# Duinopeak_Shield_Bot_v0_9.net
KiCad netlist of a schematic drawn in EAGLE
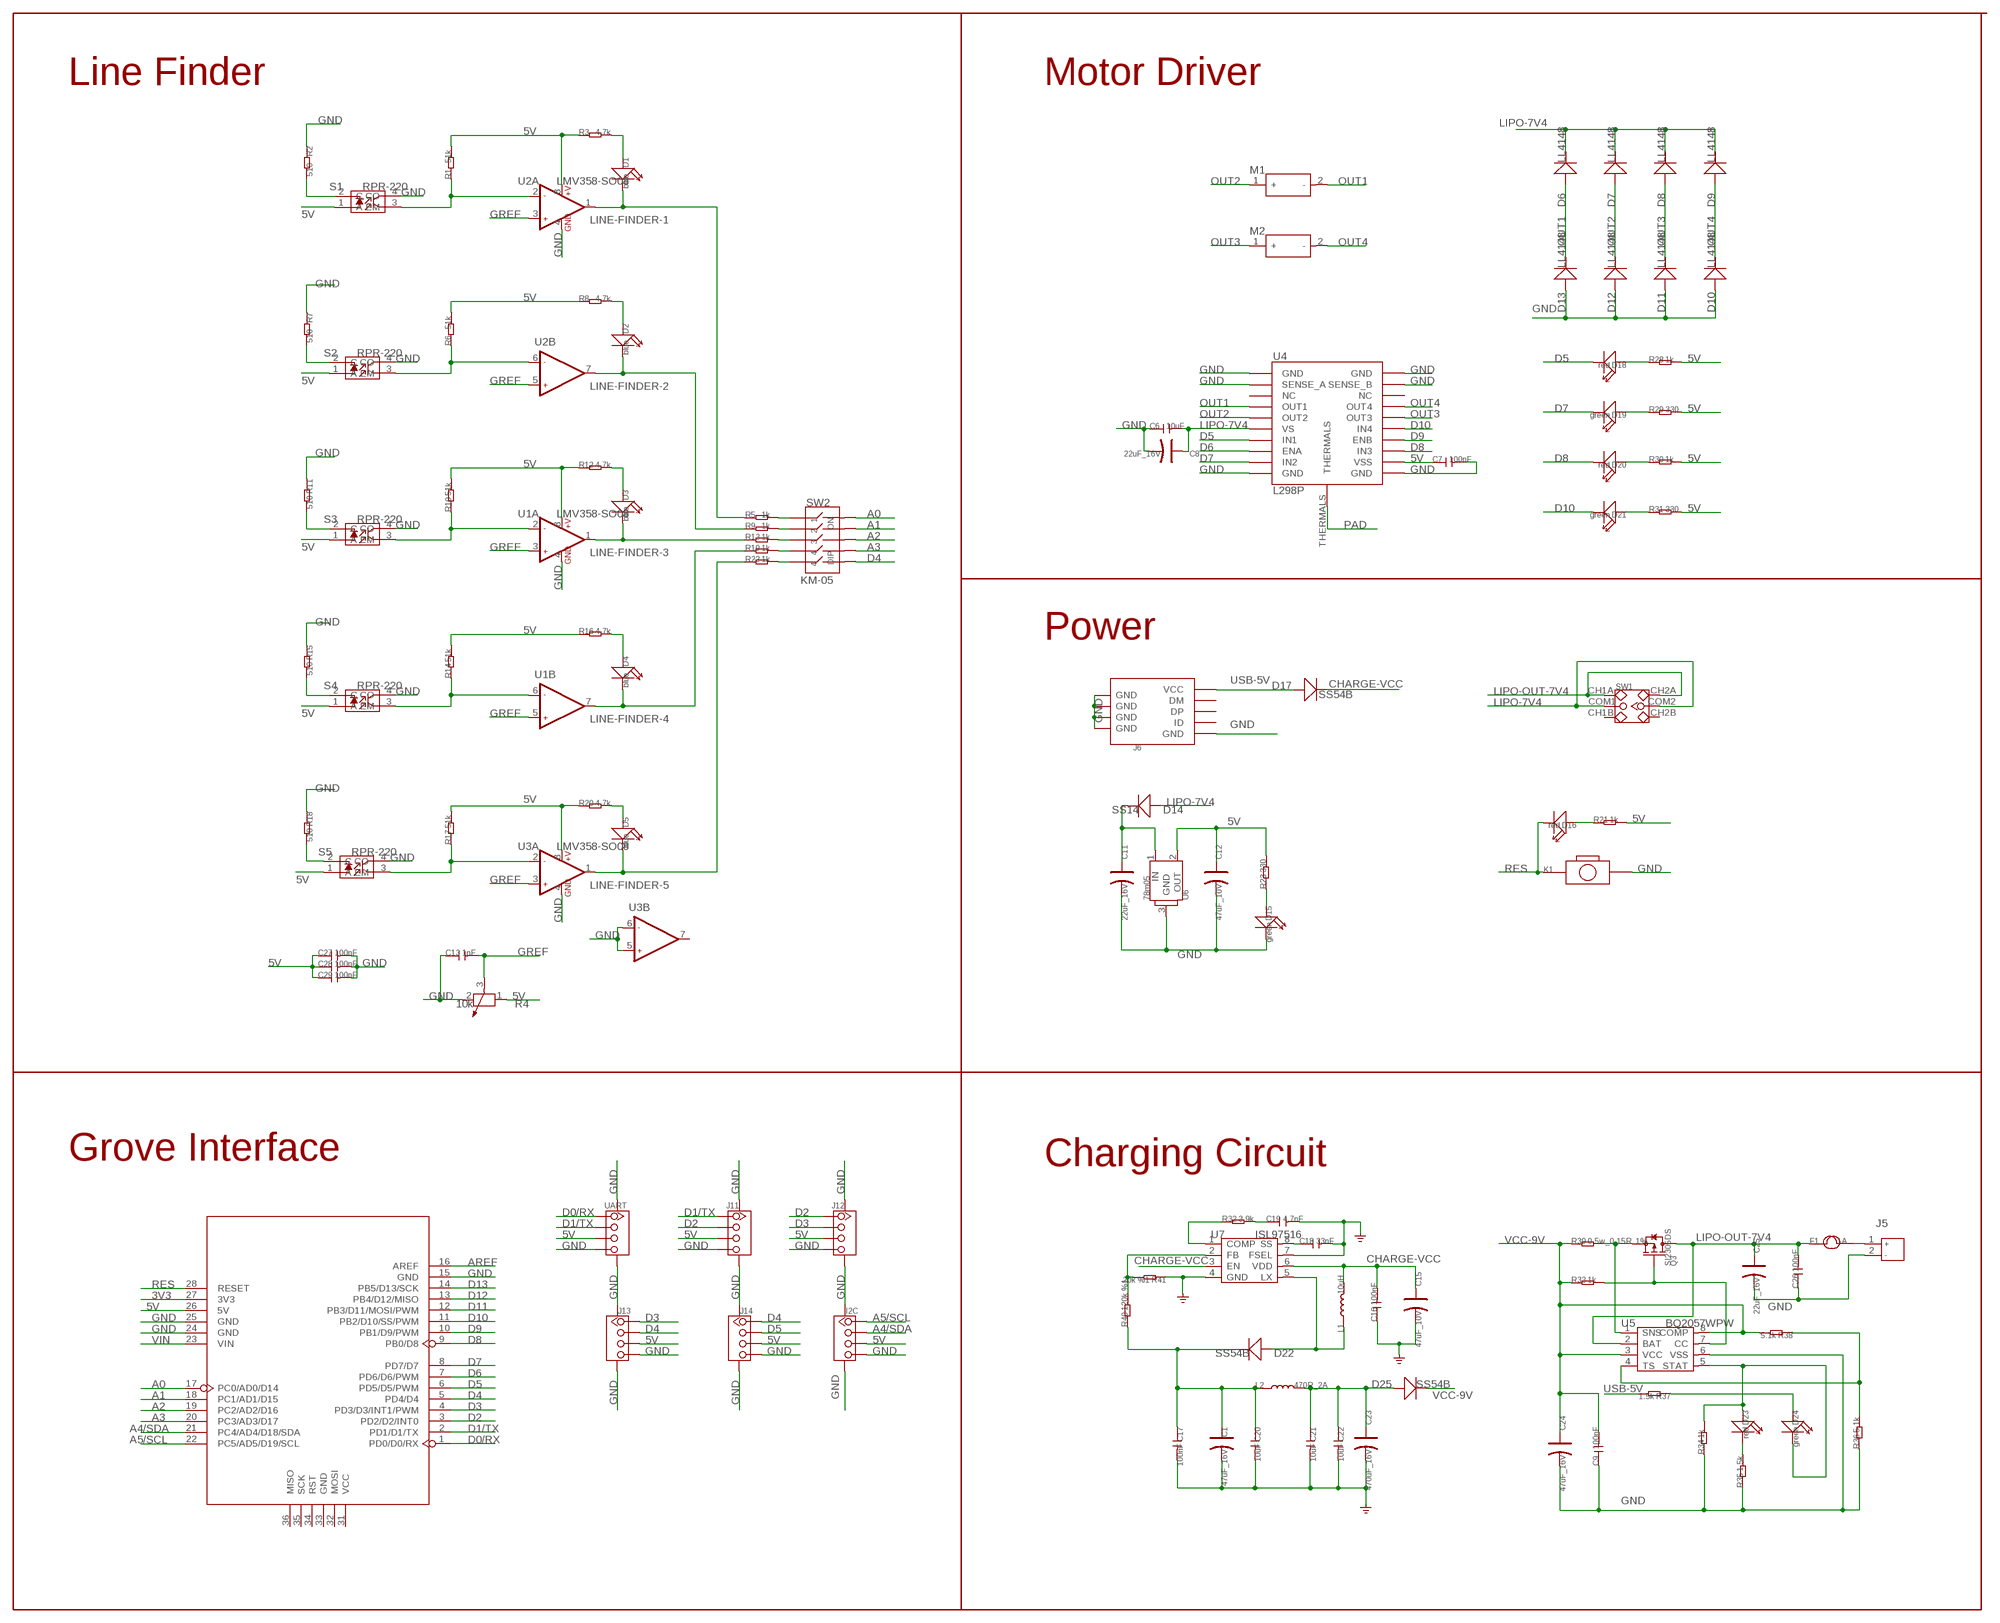
[diagram p0: schematic, sheet 1]

(export (version "E")
  (design (tool "Eeschema 10.0.6"))
  (components
    (comp (ref "C1")
      (value "47uF_16V")
      (footprint "eagle-import:AVX-C")
      (libsource (lib "eagle-import") (part "CAP-AVX-C"))
    )
    (comp (ref "C6")
      (value "10uF")
      (footprint "eagle-import:C0603")
      (libsource (lib "eagle-import") (part "C-0603"))
    )
    (comp (ref "C7")
      (value "100nF")
      (footprint "eagle-import:C0603")
      (libsource (lib "eagle-import") (part "C-0603"))
    )
    (comp (ref "C8")
      (value "22uF_16V")
      (footprint "eagle-import:AVX-B")
      (libsource (lib "eagle-import") (part "CAP-AVX-B"))
    )
    (comp (ref "C9")
      (value "100nF")
      (footprint "eagle-import:C0603")
      (libsource (lib "eagle-import") (part "C-0603"))
    )
    (comp (ref "C11")
      (value "22uF_16V")
      (footprint "eagle-import:AVX-B")
      (libsource (lib "eagle-import") (part "CAP-AVX-B"))
    )
    (comp (ref "C12")
      (value "47uF_10V")
      (footprint "eagle-import:AVX-B")
      (libsource (lib "eagle-import") (part "CAP-AVX-B"))
    )
    (comp (ref "C13")
      (value "1nF")
      (footprint "eagle-import:C0603")
      (libsource (lib "eagle-import") (part "C-0603"))
    )
    (comp (ref "C15")
      (value "47uF_10V")
      (footprint "eagle-import:AVX-B")
      (libsource (lib "eagle-import") (part "CAP-AVX-B"))
    )
    (comp (ref "C16")
      (value "100nF")
      (footprint "eagle-import:C0603")
      (libsource (lib "eagle-import") (part "C-0603"))
    )
    (comp (ref "C17")
      (value "100nF")
      (footprint "eagle-import:C0603")
      (libsource (lib "eagle-import") (part "C-0603"))
    )
    (comp (ref "C18")
      (value "33nF")
      (footprint "eagle-import:C0603")
      (libsource (lib "eagle-import") (part "C-0603"))
    )
    (comp (ref "C19")
      (value "4.7nF")
      (footprint "eagle-import:C0603")
      (libsource (lib "eagle-import") (part "C-0603"))
    )
    (comp (ref "C20")
      (value "10uF")
      (footprint "eagle-import:C0603")
      (libsource (lib "eagle-import") (part "C-0603"))
    )
    (comp (ref "C21")
      (value "10uF")
      (footprint "eagle-import:C0603")
      (libsource (lib "eagle-import") (part "C-0603"))
    )
    (comp (ref "C22")
      (value "10uF")
      (footprint "eagle-import:C0603")
      (libsource (lib "eagle-import") (part "C-0603"))
    )
    (comp (ref "C23")
      (value "470uF_16V")
      (footprint "eagle-import:AVX-E")
      (libsource (lib "eagle-import") (part "CAP-AVX-E"))
    )
    (comp (ref "C24")
      (value "47uF_16V")
      (footprint "eagle-import:AVX-C")
      (libsource (lib "eagle-import") (part "CAP-AVX-C"))
    )
    (comp (ref "C25")
      (value "22uF_16V")
      (footprint "eagle-import:AVX-B")
      (libsource (lib "eagle-import") (part "CAP-AVX-B"))
    )
    (comp (ref "C26")
      (value "100nF")
      (footprint "eagle-import:C0603")
      (libsource (lib "eagle-import") (part "C-0603"))
    )
    (comp (ref "C27")
      (value "100nF")
      (footprint "eagle-import:C0603")
      (libsource (lib "eagle-import") (part "C-0603"))
    )
    (comp (ref "C28")
      (value "100nF")
      (footprint "eagle-import:C0603")
      (libsource (lib "eagle-import") (part "C-0603"))
    )
    (comp (ref "C29")
      (value "100nF")
      (footprint "eagle-import:C0603")
      (libsource (lib "eagle-import") (part "C-0603"))
    )
    (comp (ref "D1")
      (value "blue")
      (footprint "eagle-import:LED-0603")
      (libsource (lib "eagle-import") (part "LED'0603'"))
    )
    (comp (ref "D2")
      (value "blue")
      (footprint "eagle-import:LED-0603")
      (libsource (lib "eagle-import") (part "LED'0603'"))
    )
    (comp (ref "D3")
      (value "blue")
      (footprint "eagle-import:LED-0603")
      (libsource (lib "eagle-import") (part "LED'0603'"))
    )
    (comp (ref "D4")
      (value "blue")
      (footprint "eagle-import:LED-0603")
      (libsource (lib "eagle-import") (part "LED'0603'"))
    )
    (comp (ref "D5")
      (value "blue")
      (footprint "eagle-import:LED-0603")
      (libsource (lib "eagle-import") (part "LED'0603'"))
    )
    (comp (ref "D6")
      (value "LL4148")
      (footprint "eagle-import:SOD123")
      (libsource (lib "eagle-import") (part "D'1206'"))
    )
    (comp (ref "D7")
      (value "LL4148")
      (footprint "eagle-import:SOD123")
      (libsource (lib "eagle-import") (part "D'1206'"))
    )
    (comp (ref "D8")
      (value "LL4148")
      (footprint "eagle-import:SOD123")
      (libsource (lib "eagle-import") (part "D'1206'"))
    )
    (comp (ref "D9")
      (value "LL4148")
      (footprint "eagle-import:SOD123")
      (libsource (lib "eagle-import") (part "D'1206'"))
    )
    (comp (ref "D10")
      (value "LL4148")
      (footprint "eagle-import:SOD123")
      (libsource (lib "eagle-import") (part "D'1206'"))
    )
    (comp (ref "D11")
      (value "LL4148")
      (footprint "eagle-import:SOD123")
      (libsource (lib "eagle-import") (part "D'1206'"))
    )
    (comp (ref "D12")
      (value "LL4148")
      (footprint "eagle-import:SOD123")
      (libsource (lib "eagle-import") (part "D'1206'"))
    )
    (comp (ref "D13")
      (value "LL4148")
      (footprint "eagle-import:SOD123")
      (libsource (lib "eagle-import") (part "D'1206'"))
    )
    (comp (ref "D14")
      (value "SS14")
      (footprint "eagle-import:D2010")
      (libsource (lib "eagle-import") (part "D'SMA'"))
    )
    (comp (ref "D15")
      (value "green")
      (footprint "eagle-import:LED-0603")
      (libsource (lib "eagle-import") (part "LED'0603'"))
    )
    (comp (ref "D16")
      (value "red")
      (footprint "eagle-import:LED-0603")
      (libsource (lib "eagle-import") (part "LED'0603'"))
    )
    (comp (ref "D17")
      (value "SS54B")
      (footprint "eagle-import:SMB")
      (libsource (lib "eagle-import") (part "D'MBRS240LT3'"))
    )
    (comp (ref "D18")
      (value "red")
      (footprint "eagle-import:LED-0603")
      (libsource (lib "eagle-import") (part "LED'0603'"))
    )
    (comp (ref "D19")
      (value "green")
      (footprint "eagle-import:LED-0603")
      (libsource (lib "eagle-import") (part "LED'0603'"))
    )
    (comp (ref "D20")
      (value "red")
      (footprint "eagle-import:LED-0603")
      (libsource (lib "eagle-import") (part "LED'0603'"))
    )
    (comp (ref "D21")
      (value "green")
      (footprint "eagle-import:LED-0603")
      (libsource (lib "eagle-import") (part "LED'0603'"))
    )
    (comp (ref "D22")
      (value "SS54B")
      (footprint "eagle-import:SMB")
      (libsource (lib "eagle-import") (part "D'MBRS240LT3'"))
    )
    (comp (ref "D23")
      (value "red")
      (footprint "eagle-import:LED-0603")
      (libsource (lib "eagle-import") (part "LED'0603'"))
    )
    (comp (ref "D24")
      (value "green")
      (footprint "eagle-import:LED-0603")
      (libsource (lib "eagle-import") (part "LED'0603'"))
    )
    (comp (ref "D25")
      (value "SS54B")
      (footprint "eagle-import:SMB")
      (libsource (lib "eagle-import") (part "D'MBRS240LT3'"))
    )
    (comp (ref "F1")
      (value "1A")
      (footprint "eagle-import:1812")
      (libsource (lib "eagle-import") (part "FUSE"))
    )
    (comp (ref "I2C")
      (value "TWIG-4P-2.0-SMD-FEMALE-REINFORCE'90D'")
      (footprint "eagle-import:4P-SMD-2.0-90D")
      (libsource (lib "eagle-import") (part "TWIG-4P-2.0-SMD-FEMALE-REINFORCE'90D'"))
    )
    (comp (ref "J5")
      (value "JACK-JST-2P-PW'2.0'")
      (footprint "eagle-import:JST-2.0")
      (libsource (lib "eagle-import") (part "JACK-JST-2P-PW'2.0'"))
    )
    (comp (ref "J6")
      (value "USB-MINIUSB-5P-STRONG")
      (footprint "eagle-import:MINI-SMD-5P")
      (libsource (lib "eagle-import") (part "USB-MINIUSB-5P-STRONG"))
    )
    (comp (ref "J11")
      (value "TWIG-4P-2.0-SMD-FEMALE-REINFORCE'90D'")
      (footprint "eagle-import:4P-SMD-2.0-90D")
      (libsource (lib "eagle-import") (part "TWIG-4P-2.0-SMD-FEMALE-REINFORCE'90D'"))
    )
    (comp (ref "J12")
      (value "TWIG-4P-2.0-SMD-FEMALE-REINFORCE'90D'")
      (footprint "eagle-import:4P-SMD-2.0-90D")
      (libsource (lib "eagle-import") (part "TWIG-4P-2.0-SMD-FEMALE-REINFORCE'90D'"))
    )
    (comp (ref "J13")
      (value "TWIG-4P-2.0-SMD-FEMALE-REINFORCE'90D'")
      (footprint "eagle-import:4P-SMD-2.0-90D")
      (libsource (lib "eagle-import") (part "TWIG-4P-2.0-SMD-FEMALE-REINFORCE'90D'"))
    )
    (comp (ref "J14")
      (value "TWIG-4P-2.0-SMD-FEMALE-REINFORCE'90D'")
      (footprint "eagle-import:4P-SMD-2.0-90D")
      (libsource (lib "eagle-import") (part "TWIG-4P-2.0-SMD-FEMALE-REINFORCE'90D'"))
    )
    (comp (ref "K1")
      (value "BOTTON-2P-90D")
      (footprint "eagle-import:2P-7.62X3.56-90D")
      (libsource (lib "eagle-import") (part "BOTTON-2P-90D"))
    )
    (comp (ref "L1")
      (value "10uH")
      (footprint "eagle-import:2626")
      (libsource (lib "eagle-import") (part "L'IHLP-2525BD-01'"))
    )
    (comp (ref "L2")
      (value "470R_2A")
      (footprint "eagle-import:L0805")
      (libsource (lib "eagle-import") (part "L'0805'"))
    )
    (comp (ref "M1")
      (value "MOTOR-2P-PAD")
      (footprint "eagle-import:2P-SMD-27X26")
      (libsource (lib "eagle-import") (part "MOTOR-2P-PAD"))
    )
    (comp (ref "M2")
      (value "MOTOR-2P-PAD")
      (footprint "eagle-import:2P-SMD-27X26")
      (libsource (lib "eagle-import") (part "MOTOR-2P-PAD"))
    )
    (comp (ref "Q3")
      (value "SI2305DS")
      (footprint "eagle-import:SOT23")
      (libsource (lib "eagle-import") (part "MOSFET-P'SI2323CDS/SI2305DS{lt}BR{gt}'"))
    )
    (comp (ref "R1")
      (value "51k")
      (footprint "eagle-import:R0603")
      (libsource (lib "eagle-import") (part "R-0603"))
    )
    (comp (ref "R2")
      (value "510")
      (footprint "eagle-import:R0603")
      (libsource (lib "eagle-import") (part "R-0603"))
    )
    (comp (ref "R3")
      (value "4.7k")
      (footprint "eagle-import:R0603")
      (libsource (lib "eagle-import") (part "R-0603"))
    )
    (comp (ref "R4")
      (value "10k")
      (footprint "eagle-import:3P-SQUA-7X6.8")
      (libsource (lib "eagle-import") (part "R-POTENTIOMETER'3362'"))
    )
    (comp (ref "R5")
      (value "1k")
      (footprint "eagle-import:R0603")
      (libsource (lib "eagle-import") (part "R-0603"))
    )
    (comp (ref "R6")
      (value "51k")
      (footprint "eagle-import:R0603")
      (libsource (lib "eagle-import") (part "R-0603"))
    )
    (comp (ref "R7")
      (value "510")
      (footprint "eagle-import:R0603")
      (libsource (lib "eagle-import") (part "R-0603"))
    )
    (comp (ref "R8")
      (value "4.7k")
      (footprint "eagle-import:R0603")
      (libsource (lib "eagle-import") (part "R-0603"))
    )
    (comp (ref "R9")
      (value "1k")
      (footprint "eagle-import:R0603")
      (libsource (lib "eagle-import") (part "R-0603"))
    )
    (comp (ref "R10")
      (value "51k")
      (footprint "eagle-import:R0603")
      (libsource (lib "eagle-import") (part "R-0603"))
    )
    (comp (ref "R11")
      (value "510")
      (footprint "eagle-import:R0603")
      (libsource (lib "eagle-import") (part "R-0603"))
    )
    (comp (ref "R12")
      (value "4.7k")
      (footprint "eagle-import:R0603")
      (libsource (lib "eagle-import") (part "R-0603"))
    )
    (comp (ref "R13")
      (value "1k")
      (footprint "eagle-import:R0603")
      (libsource (lib "eagle-import") (part "R-0603"))
    )
    (comp (ref "R14")
      (value "51k")
      (footprint "eagle-import:R0603")
      (libsource (lib "eagle-import") (part "R-0603"))
    )
    (comp (ref "R15")
      (value "510")
      (footprint "eagle-import:R0603")
      (libsource (lib "eagle-import") (part "R-0603"))
    )
    (comp (ref "R16")
      (value "4.7k")
      (footprint "eagle-import:R0603")
      (libsource (lib "eagle-import") (part "R-0603"))
    )
    (comp (ref "R17")
      (value "51k")
      (footprint "eagle-import:R0603")
      (libsource (lib "eagle-import") (part "R-0603"))
    )
    (comp (ref "R18")
      (value "510")
      (footprint "eagle-import:R0603")
      (libsource (lib "eagle-import") (part "R-0603"))
    )
    (comp (ref "R19")
      (value "1k")
      (footprint "eagle-import:R0603")
      (libsource (lib "eagle-import") (part "R-0603"))
    )
    (comp (ref "R20")
      (value "4.7k")
      (footprint "eagle-import:R0603")
      (libsource (lib "eagle-import") (part "R-0603"))
    )
    (comp (ref "R21")
      (value "1k")
      (footprint "eagle-import:R0603")
      (libsource (lib "eagle-import") (part "R-0603"))
    )
    (comp (ref "R22")
      (value "1k")
      (footprint "eagle-import:R0603")
      (libsource (lib "eagle-import") (part "R-0603"))
    )
    (comp (ref "R23")
      (value "330")
      (footprint "eagle-import:R0603")
      (libsource (lib "eagle-import") (part "R-0603"))
    )
    (comp (ref "R28")
      (value "1k")
      (footprint "eagle-import:R0603")
      (libsource (lib "eagle-import") (part "R-0603"))
    )
    (comp (ref "R29")
      (value "330")
      (footprint "eagle-import:R0603")
      (libsource (lib "eagle-import") (part "R-0603"))
    )
    (comp (ref "R30")
      (value "1k")
      (footprint "eagle-import:R0603")
      (libsource (lib "eagle-import") (part "R-0603"))
    )
    (comp (ref "R31")
      (value "330")
      (footprint "eagle-import:R0603")
      (libsource (lib "eagle-import") (part "R-0603"))
    )
    (comp (ref "R32")
      (value "3.9k")
      (footprint "eagle-import:R0603")
      (libsource (lib "eagle-import") (part "R-0603"))
    )
    (comp (ref "R33")
      (value "1k")
      (footprint "eagle-import:R0603")
      (libsource (lib "eagle-import") (part "R-0603"))
    )
    (comp (ref "R34")
      (value "1k")
      (footprint "eagle-import:R0603")
      (libsource (lib "eagle-import") (part "R-0603"))
    )
    (comp (ref "R35")
      (value "1.5k")
      (footprint "eagle-import:R0603")
      (libsource (lib "eagle-import") (part "R-0603"))
    )
    (comp (ref "R36")
      (value "5.1k")
      (footprint "eagle-import:R0603")
      (libsource (lib "eagle-import") (part "R-0603"))
    )
    (comp (ref "R37")
      (value "1.5k")
      (footprint "eagle-import:R0603")
      (libsource (lib "eagle-import") (part "R-0603"))
    )
    (comp (ref "R38")
      (value "5.1k")
      (footprint "eagle-import:R0603")
      (libsource (lib "eagle-import") (part "R-0603"))
    )
    (comp (ref "R39")
      (value "0.5w_0.15R 1%")
      (footprint "eagle-import:R2512")
      (libsource (lib "eagle-import") (part "R-2512"))
    )
    (comp (ref "R40")
      (value "120k %1")
      (footprint "eagle-import:R0603")
      (libsource (lib "eagle-import") (part "R-0603"))
    )
    (comp (ref "R41")
      (value "20k %1")
      (footprint "eagle-import:R0603")
      (libsource (lib "eagle-import") (part "R-0603"))
    )
    (comp (ref "S1")
      (value "RPR-220")
      (footprint "eagle-import:4P-6.4X4.9X6.5H")
      (libsource (lib "eagle-import") (part "REFLECTIVE-PHOTOSENSOR-RPR-220"))
    )
    (comp (ref "S2")
      (value "RPR-220")
      (footprint "eagle-import:4P-6.4X4.9X6.5H")
      (libsource (lib "eagle-import") (part "REFLECTIVE-PHOTOSENSOR-RPR-220"))
    )
    (comp (ref "S3")
      (value "RPR-220")
      (footprint "eagle-import:4P-6.4X4.9X6.5H")
      (libsource (lib "eagle-import") (part "REFLECTIVE-PHOTOSENSOR-RPR-220"))
    )
    (comp (ref "S4")
      (value "RPR-220")
      (footprint "eagle-import:4P-6.4X4.9X6.5H")
      (libsource (lib "eagle-import") (part "REFLECTIVE-PHOTOSENSOR-RPR-220"))
    )
    (comp (ref "S5")
      (value "RPR-220")
      (footprint "eagle-import:4P-6.4X4.9X6.5H")
      (libsource (lib "eagle-import") (part "REFLECTIVE-PHOTOSENSOR-RPR-220"))
    )
    (comp (ref "SW1")
      (value "SWITCH-2CH-6P'90D'")
      (footprint "eagle-import:6P-2CH-2.54-9.0X3.6-90D")
      (libsource (lib "eagle-import") (part "SWITCH-2CH-6P'90D'"))
    )
    (comp (ref "SW2")
      (value "KM-05")
      (footprint "eagle-import:10P-SMD-14.2X6.8")
      (libsource (lib "eagle-import") (part "SWITCH-KM-05-10P"))
    )
    (comp (ref "U1")
      (value "LMV358-SO08")
      (footprint "eagle-import:SO08")
      (libsource (lib "eagle-import") (part "LMV358-SO08"))
    )
    (comp (ref "U2")
      (value "LMV358-SO08")
      (footprint "eagle-import:SO08")
      (libsource (lib "eagle-import") (part "LMV358-SO08"))
    )
    (comp (ref "U3")
      (value "LMV358-SO08")
      (footprint "eagle-import:SO08")
      (libsource (lib "eagle-import") (part "LMV358-SO08"))
    )
    (comp (ref "U4")
      (value "L298P")
      (footprint "eagle-import:POWERSO20")
      (libsource (lib "eagle-import") (part "L298_BRIDGE_DRIVER"))
    )
    (comp (ref "U5")
      (value "BQ2057WPW")
      (footprint "eagle-import:TSSOP8")
      (libsource (lib "eagle-import") (part "BQ2057WPW"))
    )
    (comp (ref "U6")
      (value "78m05")
      (footprint "eagle-import:TO252")
      (libsource (lib "eagle-import") (part "78M05-TO252"))
    )
    (comp (ref "U7")
      (value "ISL97516")
      (footprint "eagle-import:MSOP8")
      (libsource (lib "eagle-import") (part "ISL97516"))
    )
    (comp (ref "U13")
      (value "ARDUINO")
      (footprint "eagle-import:ARDUINO")
      (libsource (lib "eagle-import") (part "ARDUINO"))
    )
    (comp (ref "UART")
      (value "TWIG-4P-2.0-SMD-FEMALE-REINFORCE'90D'")
      (footprint "eagle-import:4P-SMD-2.0-90D")
      (libsource (lib "eagle-import") (part "TWIG-4P-2.0-SMD-FEMALE-REINFORCE'90D'"))
    )
  )
  (nets
    (net (code "1") (name "/3V3") (class "Default")
      (node (ref "U13") (pin "27") (pinfunction "3V3_27") (pintype "bidirectional"))
    )
    (net (code "2") (name "/5V") (class "Default")
      (node (ref "C12") (pin "+") (pinfunction "+_+") (pintype "passive"))
      (node (ref "C27") (pin "1") (pinfunction "1_1") (pintype "passive"))
      (node (ref "C28") (pin "1") (pinfunction "1_1") (pintype "passive"))
      (node (ref "C29") (pin "1") (pinfunction "1_1") (pintype "passive"))
      (node (ref "C7") (pin "1") (pinfunction "1_1") (pintype "passive"))
      (node (ref "I2C") (pin "3") (pinfunction "3_3") (pintype "bidirectional"))
      (node (ref "J11") (pin "3") (pinfunction "3_3") (pintype "bidirectional"))
      (node (ref "J12") (pin "3") (pinfunction "3_3") (pintype "bidirectional"))
      (node (ref "J13") (pin "3") (pinfunction "3_3") (pintype "bidirectional"))
      (node (ref "J14") (pin "3") (pinfunction "3_3") (pintype "bidirectional"))
      (node (ref "R1") (pin "2") (pinfunction "2_2") (pintype "passive"))
      (node (ref "R10") (pin "2") (pinfunction "2_2") (pintype "passive"))
      (node (ref "R12") (pin "1") (pinfunction "1_1") (pintype "passive"))
      (node (ref "R14") (pin "2") (pinfunction "2_2") (pintype "passive"))
      (node (ref "R16") (pin "1") (pinfunction "1_1") (pintype "passive"))
      (node (ref "R17") (pin "2") (pinfunction "2_2") (pintype "passive"))
      (node (ref "R20") (pin "1") (pinfunction "1_1") (pintype "passive"))
      (node (ref "R21") (pin "2") (pinfunction "2_2") (pintype "passive"))
      (node (ref "R23") (pin "2") (pinfunction "2_2") (pintype "passive"))
      (node (ref "R28") (pin "2") (pinfunction "2_2") (pintype "passive"))
      (node (ref "R29") (pin "2") (pinfunction "2_2") (pintype "passive"))
      (node (ref "R3") (pin "1") (pinfunction "1_1") (pintype "passive"))
      (node (ref "R30") (pin "2") (pinfunction "2_2") (pintype "passive"))
      (node (ref "R31") (pin "2") (pinfunction "2_2") (pintype "passive"))
      (node (ref "R4") (pin "1") (pinfunction "1_1") (pintype "passive"))
      (node (ref "R6") (pin "2") (pinfunction "2_2") (pintype "passive"))
      (node (ref "R8") (pin "1") (pinfunction "1_1") (pintype "passive"))
      (node (ref "S1") (pin "1") (pinfunction "A_1") (pintype "bidirectional"))
      (node (ref "S2") (pin "1") (pinfunction "A_1") (pintype "bidirectional"))
      (node (ref "S3") (pin "1") (pinfunction "A_1") (pintype "bidirectional"))
      (node (ref "S4") (pin "1") (pinfunction "A_1") (pintype "bidirectional"))
      (node (ref "S5") (pin "1") (pinfunction "A_1") (pintype "bidirectional"))
      (node (ref "U1") (pin "8") (pinfunction "+V_8") (pintype "power_in"))
      (node (ref "U13") (pin "26") (pinfunction "5V_26") (pintype "bidirectional"))
      (node (ref "U2") (pin "8") (pinfunction "+V_8") (pintype "power_in"))
      (node (ref "U3") (pin "8") (pinfunction "+V_8") (pintype "power_in"))
      (node (ref "U4") (pin "P$12") (pinfunction "VSS_P$12") (pintype "bidirectional"))
      (node (ref "U6") (pin "2") (pinfunction "OUT_2") (pintype "bidirectional"))
      (node (ref "UART") (pin "3") (pinfunction "3_3") (pintype "bidirectional"))
    )
    (net (code "3") (name "/A0") (class "Default")
      (node (ref "SW2") (pin "10") (pinfunction "10_10") (pintype "bidirectional"))
      (node (ref "U13") (pin "17") (pinfunction "PC0/AD0/D14_17") (pintype "bidirectional"))
    )
    (net (code "4") (name "/A1") (class "Default")
      (node (ref "SW2") (pin "9") (pinfunction "9_9") (pintype "bidirectional"))
      (node (ref "U13") (pin "18") (pinfunction "PC1/AD1/D15_18") (pintype "bidirectional"))
    )
    (net (code "5") (name "/A2") (class "Default")
      (node (ref "SW2") (pin "8") (pinfunction "8_8") (pintype "bidirectional"))
      (node (ref "U13") (pin "19") (pinfunction "PC2/AD2/D16_19") (pintype "bidirectional"))
    )
    (net (code "6") (name "/A3") (class "Default")
      (node (ref "SW2") (pin "7") (pinfunction "7_7") (pintype "bidirectional"))
      (node (ref "U13") (pin "20") (pinfunction "PC3/AD3/D17_20") (pintype "bidirectional"))
    )
    (net (code "7") (name "/A4{slash}SDA") (class "Default")
      (node (ref "I2C") (pin "2") (pinfunction "2_2") (pintype "bidirectional"))
      (node (ref "U13") (pin "21") (pinfunction "PC4/AD4/D18/SDA_21") (pintype "bidirectional"))
    )
    (net (code "8") (name "/A5{slash}SCL") (class "Default")
      (node (ref "I2C") (pin "1") (pinfunction "1_1") (pintype "bidirectional"))
      (node (ref "U13") (pin "22") (pinfunction "PC5/AD5/D19/SCL_22") (pintype "bidirectional"))
    )
    (net (code "9") (name "/AREF") (class "Default")
      (node (ref "U13") (pin "16") (pinfunction "AREF_16") (pintype "bidirectional"))
    )
    (net (code "10") (name "/CHARGE-VCC") (class "Default")
      (node (ref "C15") (pin "+") (pinfunction "+_+") (pintype "passive"))
      (node (ref "C16") (pin "2") (pinfunction "2_2") (pintype "passive"))
      (node (ref "D17") (pin "-") (pinfunction "-_-") (pintype "passive"))
      (node (ref "L1") (pin "2") (pinfunction "2_2") (pintype "passive"))
      (node (ref "U7") (pin "3") (pinfunction "EN_3") (pintype "input"))
      (node (ref "U7") (pin "6") (pinfunction "VDD_6") (pintype "power_in"))
    )
    (net (code "11") (name "/D0{slash}RX") (class "Default")
      (node (ref "U13") (pin "1") (pinfunction "PD0/D0/RX_1") (pintype "bidirectional"))
      (node (ref "UART") (pin "1") (pinfunction "1_1") (pintype "bidirectional"))
    )
    (net (code "12") (name "/D1{slash}TX") (class "Default")
      (node (ref "J11") (pin "1") (pinfunction "1_1") (pintype "bidirectional"))
      (node (ref "U13") (pin "2") (pinfunction "PD1/D1/TX_2") (pintype "bidirectional"))
      (node (ref "UART") (pin "2") (pinfunction "2_2") (pintype "bidirectional"))
    )
    (net (code "13") (name "/D2") (class "Default")
      (node (ref "J11") (pin "2") (pinfunction "2_2") (pintype "bidirectional"))
      (node (ref "J12") (pin "1") (pinfunction "1_1") (pintype "bidirectional"))
      (node (ref "U13") (pin "3") (pinfunction "PD2/D2/INT0_3") (pintype "bidirectional"))
    )
    (net (code "14") (name "/D3") (class "Default")
      (node (ref "J12") (pin "2") (pinfunction "2_2") (pintype "bidirectional"))
      (node (ref "J13") (pin "1") (pinfunction "1_1") (pintype "bidirectional"))
      (node (ref "U13") (pin "4") (pinfunction "PD3/D3/INT1/PWM_4") (pintype "bidirectional"))
    )
    (net (code "15") (name "/D4") (class "Default")
      (node (ref "J13") (pin "2") (pinfunction "2_2") (pintype "bidirectional"))
      (node (ref "J14") (pin "1") (pinfunction "1_1") (pintype "bidirectional"))
      (node (ref "SW2") (pin "6") (pinfunction "6_6") (pintype "bidirectional"))
      (node (ref "U13") (pin "5") (pinfunction "PD4/D4_5") (pintype "bidirectional"))
    )
    (net (code "16") (name "/D5") (class "Default")
      (node (ref "D18") (pin "-") (pinfunction "-_-") (pintype "passive"))
      (node (ref "J14") (pin "2") (pinfunction "2_2") (pintype "bidirectional"))
      (node (ref "U13") (pin "6") (pinfunction "PD5/D5/PWM_6") (pintype "bidirectional"))
      (node (ref "U4") (pin "P$7") (pinfunction "IN1_P$7") (pintype "bidirectional"))
    )
    (net (code "17") (name "/D6") (class "Default")
      (node (ref "U13") (pin "7") (pinfunction "PD6/D6/PWM_7") (pintype "bidirectional"))
      (node (ref "U4") (pin "P$8") (pinfunction "ENA_P$8") (pintype "bidirectional"))
    )
    (net (code "18") (name "/D7") (class "Default")
      (node (ref "D19") (pin "-") (pinfunction "-_-") (pintype "passive"))
      (node (ref "U13") (pin "8") (pinfunction "PD7/D7_8") (pintype "bidirectional"))
      (node (ref "U4") (pin "P$9") (pinfunction "IN2_P$9") (pintype "bidirectional"))
    )
    (net (code "19") (name "/D8") (class "Default")
      (node (ref "D20") (pin "-") (pinfunction "-_-") (pintype "passive"))
      (node (ref "U13") (pin "9") (pinfunction "PB0/D8_9") (pintype "bidirectional"))
      (node (ref "U4") (pin "P$13") (pinfunction "IN3_P$13") (pintype "bidirectional"))
    )
    (net (code "20") (name "/D9") (class "Default")
      (node (ref "U13") (pin "10") (pinfunction "PB1/D9/PWM_10") (pintype "bidirectional"))
      (node (ref "U4") (pin "P$14") (pinfunction "ENB_P$14") (pintype "bidirectional"))
    )
    (net (code "21") (name "/D10") (class "Default")
      (node (ref "D21") (pin "-") (pinfunction "-_-") (pintype "passive"))
      (node (ref "U13") (pin "11") (pinfunction "PB2/D10/SS/PWM_11") (pintype "bidirectional"))
      (node (ref "U4") (pin "P$15") (pinfunction "IN4_P$15") (pintype "bidirectional"))
    )
    (net (code "22") (name "/D11") (class "Default")
      (node (ref "U13") (pin "12") (pinfunction "PB3/D11/MOSI/PWM_12") (pintype "bidirectional"))
    )
    (net (code "23") (name "/D12") (class "Default")
      (node (ref "U13") (pin "13") (pinfunction "PB4/D12/MISO_13") (pintype "bidirectional"))
    )
    (net (code "24") (name "/D13") (class "Default")
      (node (ref "U13") (pin "14") (pinfunction "PB5/D13/SCK_14") (pintype "bidirectional"))
    )
    (net (code "25") (name "/GREF") (class "Default")
      (node (ref "C13") (pin "2") (pinfunction "2_2") (pintype "passive"))
      (node (ref "R4") (pin "3") (pinfunction "3_3") (pintype "passive"))
      (node (ref "U1") (pin "3") (pinfunction "+IN1_3") (pintype "input"))
      (node (ref "U1") (pin "5") (pinfunction "+IN2_5") (pintype "input"))
      (node (ref "U2") (pin "3") (pinfunction "+IN1_3") (pintype "input"))
      (node (ref "U2") (pin "5") (pinfunction "+IN2_5") (pintype "input"))
      (node (ref "U3") (pin "3") (pinfunction "+IN1_3") (pintype "input"))
    )
    (net (code "26") (name "/LINE-FINDER-1") (class "Default")
      (node (ref "D1") (pin "-") (pinfunction "-_-") (pintype "passive"))
      (node (ref "R5") (pin "1") (pinfunction "1_1") (pintype "passive"))
      (node (ref "U2") (pin "1") (pinfunction "OUT1_1") (pintype "output"))
    )
    (net (code "27") (name "/LINE-FINDER-2") (class "Default")
      (node (ref "D2") (pin "-") (pinfunction "-_-") (pintype "passive"))
      (node (ref "R9") (pin "1") (pinfunction "1_1") (pintype "passive"))
      (node (ref "U2") (pin "7") (pinfunction "OUT2_7") (pintype "output"))
    )
    (net (code "28") (name "/LINE-FINDER-3") (class "Default")
      (node (ref "D3") (pin "-") (pinfunction "-_-") (pintype "passive"))
      (node (ref "R13") (pin "1") (pinfunction "1_1") (pintype "passive"))
      (node (ref "U1") (pin "1") (pinfunction "OUT1_1") (pintype "output"))
    )
    (net (code "29") (name "/LINE-FINDER-4") (class "Default")
      (node (ref "D4") (pin "-") (pinfunction "-_-") (pintype "passive"))
      (node (ref "R19") (pin "1") (pinfunction "1_1") (pintype "passive"))
      (node (ref "U1") (pin "7") (pinfunction "OUT2_7") (pintype "output"))
    )
    (net (code "30") (name "/LINE-FINDER-5") (class "Default")
      (node (ref "D5") (pin "-") (pinfunction "-_-") (pintype "passive"))
      (node (ref "R22") (pin "1") (pinfunction "1_1") (pintype "passive"))
      (node (ref "U3") (pin "1") (pinfunction "OUT1_1") (pintype "output"))
    )
    (net (code "31") (name "/LIPO-7V4") (class "Default")
      (node (ref "C6") (pin "2") (pinfunction "2_2") (pintype "passive"))
      (node (ref "C8") (pin "+") (pinfunction "+_+") (pintype "passive"))
      (node (ref "D14") (pin "+") (pinfunction "+_+") (pintype "passive"))
      (node (ref "D6") (pin "-") (pinfunction "-_-") (pintype "passive"))
      (node (ref "D7") (pin "-") (pinfunction "-_-") (pintype "passive"))
      (node (ref "D8") (pin "-") (pinfunction "-_-") (pintype "passive"))
      (node (ref "D9") (pin "-") (pinfunction "-_-") (pintype "passive"))
      (node (ref "SW1") (pin "COM1") (pinfunction "COM1_COM1") (pintype "bidirectional"))
      (node (ref "SW1") (pin "COM2") (pinfunction "COM2_COM2") (pintype "bidirectional"))
      (node (ref "U4") (pin "P$6") (pinfunction "VS_P$6") (pintype "bidirectional"))
    )
    (net (code "32") (name "/LIPO-OUT-7V4") (class "Default")
      (node (ref "C25") (pin "+") (pinfunction "+_+") (pintype "passive"))
      (node (ref "C26") (pin "2") (pinfunction "2_2") (pintype "passive"))
      (node (ref "F1") (pin "1") (pinfunction "1_1") (pintype "bidirectional"))
      (node (ref "Q3") (pin "3") (pinfunction "D_3") (pintype "passive"))
      (node (ref "SW1") (pin "CH1A") (pinfunction "CH1A_CH1A") (pintype "bidirectional"))
      (node (ref "SW1") (pin "CH2A") (pinfunction "CH2A_CH2A") (pintype "bidirectional"))
      (node (ref "U5") (pin "2") (pinfunction "BAT_2") (pintype "input"))
    )
    (net (code "33") (name "/OUT1") (class "Default")
      (node (ref "D13") (pin "-") (pinfunction "-_-") (pintype "passive"))
      (node (ref "D6") (pin "+") (pinfunction "+_+") (pintype "passive"))
      (node (ref "M1") (pin "2") (pinfunction "-_2") (pintype "bidirectional"))
      (node (ref "U4") (pin "P$4") (pinfunction "OUT1_P$4") (pintype "bidirectional"))
    )
    (net (code "34") (name "/OUT2") (class "Default")
      (node (ref "D12") (pin "-") (pinfunction "-_-") (pintype "passive"))
      (node (ref "D7") (pin "+") (pinfunction "+_+") (pintype "passive"))
      (node (ref "M1") (pin "1") (pinfunction "+_1") (pintype "bidirectional"))
      (node (ref "U4") (pin "P$5") (pinfunction "OUT2_P$5") (pintype "bidirectional"))
    )
    (net (code "35") (name "/OUT3") (class "Default")
      (node (ref "D11") (pin "-") (pinfunction "-_-") (pintype "passive"))
      (node (ref "D8") (pin "+") (pinfunction "+_+") (pintype "passive"))
      (node (ref "M2") (pin "1") (pinfunction "+_1") (pintype "bidirectional"))
      (node (ref "U4") (pin "P$16") (pinfunction "OUT3_P$16") (pintype "bidirectional"))
    )
    (net (code "36") (name "/OUT4") (class "Default")
      (node (ref "D10") (pin "-") (pinfunction "-_-") (pintype "passive"))
      (node (ref "D9") (pin "+") (pinfunction "+_+") (pintype "passive"))
      (node (ref "M2") (pin "2") (pinfunction "-_2") (pintype "bidirectional"))
      (node (ref "U4") (pin "P$17") (pinfunction "OUT4_P$17") (pintype "bidirectional"))
    )
    (net (code "37") (name "/PAD") (class "Default")
      (node (ref "U4") (pin "THERMALS") (pinfunction "THERMALS_THERMALS") (pintype "bidirectional"))
    )
    (net (code "38") (name "/RES") (class "Default")
      (node (ref "D16") (pin "-") (pinfunction "-_-") (pintype "passive"))
      (node (ref "K1") (pin "P$1") (pinfunction "1_P$1") (pintype "bidirectional"))
      (node (ref "U13") (pin "28") (pinfunction "RESET_28") (pintype "bidirectional"))
    )
    (net (code "39") (name "/USB-5V") (class "Default")
      (node (ref "D17") (pin "+") (pinfunction "+_+") (pintype "passive"))
      (node (ref "J6") (pin "1") (pinfunction "VCC_1") (pintype "bidirectional"))
      (node (ref "R37") (pin "2") (pinfunction "2_2") (pintype "passive"))
    )
    (net (code "40") (name "/VCC-9V") (class "Default")
      (node (ref "C24") (pin "+") (pinfunction "+_+") (pintype "passive"))
      (node (ref "C9") (pin "2") (pinfunction "2_2") (pintype "passive"))
      (node (ref "D25") (pin "-") (pinfunction "-_-") (pintype "passive"))
      (node (ref "R33") (pin "1") (pinfunction "1_1") (pintype "passive"))
      (node (ref "R38") (pin "2") (pinfunction "2_2") (pintype "passive"))
      (node (ref "R39") (pin "1") (pinfunction "1_1") (pintype "passive"))
      (node (ref "U5") (pin "3") (pinfunction "VCC_3") (pintype "input"))
      (node (ref "U5") (pin "8") (pinfunction "COMP_8") (pintype "input"))
    )
    (net (code "41") (name "/VIN") (class "Default")
      (node (ref "U13") (pin "23") (pinfunction "VIN_23") (pintype "bidirectional"))
    )
    (net (code "42") (name "GND_POWER") (class "Default")
      (node (ref "C1") (pin "-") (pinfunction "-_-") (pintype "passive"))
      (node (ref "C11") (pin "-") (pinfunction "-_-") (pintype "passive"))
      (node (ref "C12") (pin "-") (pinfunction "-_-") (pintype "passive"))
      (node (ref "C13") (pin "1") (pinfunction "1_1") (pintype "passive"))
      (node (ref "C15") (pin "-") (pinfunction "-_-") (pintype "passive"))
      (node (ref "C16") (pin "1") (pinfunction "1_1") (pintype "passive"))
      (node (ref "C17") (pin "2") (pinfunction "2_2") (pintype "passive"))
      (node (ref "C18") (pin "2") (pinfunction "2_2") (pintype "passive"))
      (node (ref "C19") (pin "2") (pinfunction "2_2") (pintype "passive"))
      (node (ref "C20") (pin "2") (pinfunction "2_2") (pintype "passive"))
      (node (ref "C21") (pin "2") (pinfunction "2_2") (pintype "passive"))
      (node (ref "C22") (pin "2") (pinfunction "2_2") (pintype "passive"))
      (node (ref "C23") (pin "-") (pinfunction "-_-") (pintype "passive"))
      (node (ref "C24") (pin "-") (pinfunction "-_-") (pintype "passive"))
      (node (ref "C25") (pin "-") (pinfunction "-_-") (pintype "passive"))
      (node (ref "C26") (pin "1") (pinfunction "1_1") (pintype "passive"))
      (node (ref "C27") (pin "2") (pinfunction "2_2") (pintype "passive"))
      (node (ref "C28") (pin "2") (pinfunction "2_2") (pintype "passive"))
      (node (ref "C29") (pin "2") (pinfunction "2_2") (pintype "passive"))
      (node (ref "C6") (pin "1") (pinfunction "1_1") (pintype "passive"))
      (node (ref "C7") (pin "2") (pinfunction "2_2") (pintype "passive"))
      (node (ref "C8") (pin "-") (pinfunction "-_-") (pintype "passive"))
      (node (ref "C9") (pin "1") (pinfunction "1_1") (pintype "passive"))
      (node (ref "D10") (pin "+") (pinfunction "+_+") (pintype "passive"))
      (node (ref "D11") (pin "+") (pinfunction "+_+") (pintype "passive"))
      (node (ref "D12") (pin "+") (pinfunction "+_+") (pintype "passive"))
      (node (ref "D13") (pin "+") (pinfunction "+_+") (pintype "passive"))
      (node (ref "D15") (pin "-") (pinfunction "-_-") (pintype "passive"))
      (node (ref "I2C") (pin "4") (pinfunction "4_4") (pintype "bidirectional"))
      (node (ref "I2C") (pin "SS1") (pinfunction "SS1_SS1") (pintype "bidirectional"))
      (node (ref "I2C") (pin "SS2") (pinfunction "SS2_SS2") (pintype "bidirectional"))
      (node (ref "J11") (pin "4") (pinfunction "4_4") (pintype "bidirectional"))
      (node (ref "J11") (pin "SS1") (pinfunction "SS1_SS1") (pintype "bidirectional"))
      (node (ref "J11") (pin "SS2") (pinfunction "SS2_SS2") (pintype "bidirectional"))
      (node (ref "J12") (pin "4") (pinfunction "4_4") (pintype "bidirectional"))
      (node (ref "J12") (pin "SS1") (pinfunction "SS1_SS1") (pintype "bidirectional"))
      (node (ref "J12") (pin "SS2") (pinfunction "SS2_SS2") (pintype "bidirectional"))
      (node (ref "J13") (pin "4") (pinfunction "4_4") (pintype "bidirectional"))
      (node (ref "J13") (pin "SS1") (pinfunction "SS1_SS1") (pintype "bidirectional"))
      (node (ref "J13") (pin "SS2") (pinfunction "SS2_SS2") (pintype "bidirectional"))
      (node (ref "J14") (pin "4") (pinfunction "4_4") (pintype "bidirectional"))
      (node (ref "J14") (pin "SS1") (pinfunction "SS1_SS1") (pintype "bidirectional"))
      (node (ref "J14") (pin "SS2") (pinfunction "SS2_SS2") (pintype "bidirectional"))
      (node (ref "J5") (pin "2") (pinfunction "P$2_2") (pintype "bidirectional"))
      (node (ref "J6") (pin "5") (pinfunction "GND_5") (pintype "bidirectional"))
      (node (ref "J6") (pin "GND@1") (pinfunction "GND_GND@1") (pintype "bidirectional"))
      (node (ref "J6") (pin "GND@2") (pinfunction "GND_GND@2") (pintype "bidirectional"))
      (node (ref "J6") (pin "GND@3") (pinfunction "GND_GND@3") (pintype "bidirectional"))
      (node (ref "J6") (pin "GND@4") (pinfunction "GND_GND@4") (pintype "bidirectional"))
      (node (ref "K1") (pin "P$2") (pinfunction "2_P$2") (pintype "bidirectional"))
      (node (ref "R11") (pin "1") (pinfunction "1_1") (pintype "passive"))
      (node (ref "R15") (pin "1") (pinfunction "1_1") (pintype "passive"))
      (node (ref "R18") (pin "1") (pinfunction "1_1") (pintype "passive"))
      (node (ref "R2") (pin "1") (pinfunction "1_1") (pintype "passive"))
      (node (ref "R34") (pin "1") (pinfunction "1_1") (pintype "passive"))
      (node (ref "R35") (pin "1") (pinfunction "1_1") (pintype "passive"))
      (node (ref "R36") (pin "1") (pinfunction "1_1") (pintype "passive"))
      (node (ref "R4") (pin "2") (pinfunction "2_2") (pintype "passive"))
      (node (ref "R41") (pin "1") (pinfunction "1_1") (pintype "passive"))
      (node (ref "R7") (pin "1") (pinfunction "1_1") (pintype "passive"))
      (node (ref "S1") (pin "4") (pinfunction "CO_4") (pintype "bidirectional"))
      (node (ref "S2") (pin "4") (pinfunction "CO_4") (pintype "bidirectional"))
      (node (ref "S3") (pin "4") (pinfunction "CO_4") (pintype "bidirectional"))
      (node (ref "S4") (pin "4") (pinfunction "CO_4") (pintype "bidirectional"))
      (node (ref "S5") (pin "4") (pinfunction "CO_4") (pintype "bidirectional"))
      (node (ref "U1") (pin "4") (pinfunction "GND_4") (pintype "power_in"))
      (node (ref "U13") (pin "15") (pinfunction "GND_15") (pintype "bidirectional"))
      (node (ref "U13") (pin "24") (pinfunction "GND_24") (pintype "bidirectional"))
      (node (ref "U13") (pin "25") (pinfunction "GND_25") (pintype "bidirectional"))
      (node (ref "U2") (pin "4") (pinfunction "GND_4") (pintype "power_in"))
      (node (ref "U3") (pin "4") (pinfunction "GND_4") (pintype "power_in"))
      (node (ref "U3") (pin "5") (pinfunction "+IN2_5") (pintype "input"))
      (node (ref "U3") (pin "6") (pinfunction "-IN2_6") (pintype "input"))
      (node (ref "U4") (pin "P$1") (pinfunction "GND_P$1") (pintype "bidirectional"))
      (node (ref "U4") (pin "P$10") (pinfunction "GND_P$10") (pintype "bidirectional"))
      (node (ref "U4") (pin "P$11") (pinfunction "GND_P$11") (pintype "bidirectional"))
      (node (ref "U4") (pin "P$19") (pinfunction "SENSE_B_P$19") (pintype "bidirectional"))
      (node (ref "U4") (pin "P$2") (pinfunction "SENSE_A_P$2") (pintype "bidirectional"))
      (node (ref "U4") (pin "P$20") (pinfunction "GND_P$20") (pintype "bidirectional"))
      (node (ref "U5") (pin "6") (pinfunction "VSS_6") (pintype "power_in"))
      (node (ref "U6") (pin "3") (pinfunction "GND_3") (pintype "bidirectional"))
      (node (ref "U7") (pin "4") (pinfunction "GND_4") (pintype "power_in"))
      (node (ref "U7") (pin "7") (pinfunction "FSEL_7") (pintype "bidirectional"))
      (node (ref "UART") (pin "4") (pinfunction "4_4") (pintype "bidirectional"))
      (node (ref "UART") (pin "SS1") (pinfunction "SS1_SS1") (pintype "bidirectional"))
      (node (ref "UART") (pin "SS2") (pinfunction "SS2_SS2") (pintype "bidirectional"))
    )
    (net (code "43") (name "Net-(C1-Pad+)") (class "Default")
      (node (ref "C1") (pin "+") (pinfunction "+_+") (pintype "passive"))
      (node (ref "C17") (pin "1") (pinfunction "1_1") (pintype "passive"))
      (node (ref "C20") (pin "1") (pinfunction "1_1") (pintype "passive"))
      (node (ref "D22") (pin "-") (pinfunction "-_-") (pintype "passive"))
      (node (ref "L2") (pin "1") (pinfunction "1_1") (pintype "passive"))
      (node (ref "R40") (pin "1") (pinfunction "1_1") (pintype "passive"))
    )
    (net (code "44") (name "Net-(C19-Pad1)") (class "Default")
      (node (ref "C19") (pin "1") (pinfunction "1_1") (pintype "passive"))
      (node (ref "R32") (pin "2") (pinfunction "2_2") (pintype "passive"))
    )
    (net (code "45") (name "Net-(C21-Pad1)") (class "Default")
      (node (ref "C21") (pin "1") (pinfunction "1_1") (pintype "passive"))
      (node (ref "C22") (pin "1") (pinfunction "1_1") (pintype "passive"))
      (node (ref "C23") (pin "+") (pinfunction "+_+") (pintype "passive"))
      (node (ref "D25") (pin "+") (pinfunction "+_+") (pintype "passive"))
      (node (ref "L2") (pin "2") (pinfunction "2_2") (pintype "passive"))
    )
    (net (code "46") (name "Net-(D1-Pad+)") (class "Default")
      (node (ref "D1") (pin "+") (pinfunction "+_+") (pintype "passive"))
      (node (ref "R3") (pin "2") (pinfunction "2_2") (pintype "passive"))
    )
    (net (code "47") (name "Net-(D2-Pad+)") (class "Default")
      (node (ref "D2") (pin "+") (pinfunction "+_+") (pintype "passive"))
      (node (ref "R8") (pin "2") (pinfunction "2_2") (pintype "passive"))
    )
    (net (code "48") (name "Net-(D3-Pad+)") (class "Default")
      (node (ref "D3") (pin "+") (pinfunction "+_+") (pintype "passive"))
      (node (ref "R12") (pin "2") (pinfunction "2_2") (pintype "passive"))
    )
    (net (code "49") (name "Net-(D4-Pad+)") (class "Default")
      (node (ref "D4") (pin "+") (pinfunction "+_+") (pintype "passive"))
      (node (ref "R16") (pin "2") (pinfunction "2_2") (pintype "passive"))
    )
    (net (code "50") (name "Net-(D5-Pad+)") (class "Default")
      (node (ref "D5") (pin "+") (pinfunction "+_+") (pintype "passive"))
      (node (ref "R20") (pin "2") (pinfunction "2_2") (pintype "passive"))
    )
    (net (code "51") (name "Net-(D15-Pad+)") (class "Default")
      (node (ref "D15") (pin "+") (pinfunction "+_+") (pintype "passive"))
      (node (ref "R23") (pin "1") (pinfunction "1_1") (pintype "passive"))
    )
    (net (code "52") (name "Net-(D16-Pad+)") (class "Default")
      (node (ref "D16") (pin "+") (pinfunction "+_+") (pintype "passive"))
      (node (ref "R21") (pin "1") (pinfunction "1_1") (pintype "passive"))
    )
    (net (code "53") (name "Net-(D18-Pad+)") (class "Default")
      (node (ref "D18") (pin "+") (pinfunction "+_+") (pintype "passive"))
      (node (ref "R28") (pin "1") (pinfunction "1_1") (pintype "passive"))
    )
    (net (code "54") (name "Net-(D19-Pad+)") (class "Default")
      (node (ref "D19") (pin "+") (pinfunction "+_+") (pintype "passive"))
      (node (ref "R29") (pin "1") (pinfunction "1_1") (pintype "passive"))
    )
    (net (code "55") (name "Net-(D20-Pad+)") (class "Default")
      (node (ref "D20") (pin "+") (pinfunction "+_+") (pintype "passive"))
      (node (ref "R30") (pin "1") (pinfunction "1_1") (pintype "passive"))
    )
    (net (code "56") (name "Net-(D21-Pad+)") (class "Default")
      (node (ref "D21") (pin "+") (pinfunction "+_+") (pintype "passive"))
      (node (ref "R31") (pin "1") (pinfunction "1_1") (pintype "passive"))
    )
    (net (code "57") (name "Net-(D23-Pad-)") (class "Default")
      (node (ref "D23") (pin "-") (pinfunction "-_-") (pintype "passive"))
      (node (ref "R35") (pin "2") (pinfunction "2_2") (pintype "passive"))
    )
    (net (code "58") (name "Net-(D24-Pad+)") (class "Default")
      (node (ref "D24") (pin "+") (pinfunction "+_+") (pintype "passive"))
      (node (ref "R37") (pin "1") (pinfunction "1_1") (pintype "passive"))
    )
    (net (code "59") (name "Net-(J5-P$1)") (class "Default")
      (node (ref "F1") (pin "2") (pinfunction "2_2") (pintype "bidirectional"))
      (node (ref "J5") (pin "1") (pinfunction "P$1_1") (pintype "bidirectional"))
    )
    (net (code "60") (name "Net-(Q3-G)") (class "Default")
      (node (ref "Q3") (pin "1") (pinfunction "G_1") (pintype "passive"))
      (node (ref "R33") (pin "2") (pinfunction "2_2") (pintype "passive"))
      (node (ref "U5") (pin "7") (pinfunction "CC_7") (pintype "output"))
    )
    (net (code "61") (name "Net-(Q3-S)") (class "Default")
      (node (ref "Q3") (pin "2") (pinfunction "S_2") (pintype "passive"))
      (node (ref "R39") (pin "2") (pinfunction "2_2") (pintype "passive"))
      (node (ref "U5") (pin "1") (pinfunction "SNS_1") (pintype "input"))
    )
    (net (code "62") (name "Net-(R5-Pad2)") (class "Default")
      (node (ref "R5") (pin "2") (pinfunction "2_2") (pintype "passive"))
      (node (ref "SW2") (pin "1") (pinfunction "1_1") (pintype "bidirectional"))
    )
    (net (code "63") (name "Net-(R9-Pad2)") (class "Default")
      (node (ref "R9") (pin "2") (pinfunction "2_2") (pintype "passive"))
      (node (ref "SW2") (pin "2") (pinfunction "2_2") (pintype "bidirectional"))
    )
    (net (code "64") (name "Net-(R13-Pad2)") (class "Default")
      (node (ref "R13") (pin "2") (pinfunction "2_2") (pintype "passive"))
      (node (ref "SW2") (pin "3") (pinfunction "3_3") (pintype "bidirectional"))
    )
    (net (code "65") (name "Net-(R19-Pad2)") (class "Default")
      (node (ref "R19") (pin "2") (pinfunction "2_2") (pintype "passive"))
      (node (ref "SW2") (pin "4") (pinfunction "4_4") (pintype "bidirectional"))
    )
    (net (code "66") (name "Net-(R22-Pad2)") (class "Default")
      (node (ref "R22") (pin "2") (pinfunction "2_2") (pintype "passive"))
      (node (ref "SW2") (pin "5") (pinfunction "5_5") (pintype "bidirectional"))
    )
    (net (code "67") (name "Net-(S1-C)") (class "Default")
      (node (ref "R2") (pin "2") (pinfunction "2_2") (pintype "passive"))
      (node (ref "S1") (pin "2") (pinfunction "C_2") (pintype "bidirectional"))
    )
    (net (code "68") (name "Net-(S1-EM)") (class "Default")
      (node (ref "R1") (pin "1") (pinfunction "1_1") (pintype "passive"))
      (node (ref "S1") (pin "3") (pinfunction "EM_3") (pintype "bidirectional"))
      (node (ref "U2") (pin "2") (pinfunction "-IN1_2") (pintype "input"))
    )
    (net (code "69") (name "Net-(S2-C)") (class "Default")
      (node (ref "R7") (pin "2") (pinfunction "2_2") (pintype "passive"))
      (node (ref "S2") (pin "2") (pinfunction "C_2") (pintype "bidirectional"))
    )
    (net (code "70") (name "Net-(S2-EM)") (class "Default")
      (node (ref "R6") (pin "1") (pinfunction "1_1") (pintype "passive"))
      (node (ref "S2") (pin "3") (pinfunction "EM_3") (pintype "bidirectional"))
      (node (ref "U2") (pin "6") (pinfunction "-IN2_6") (pintype "input"))
    )
    (net (code "71") (name "Net-(S3-C)") (class "Default")
      (node (ref "R11") (pin "2") (pinfunction "2_2") (pintype "passive"))
      (node (ref "S3") (pin "2") (pinfunction "C_2") (pintype "bidirectional"))
    )
    (net (code "72") (name "Net-(S3-EM)") (class "Default")
      (node (ref "R10") (pin "1") (pinfunction "1_1") (pintype "passive"))
      (node (ref "S3") (pin "3") (pinfunction "EM_3") (pintype "bidirectional"))
      (node (ref "U1") (pin "2") (pinfunction "-IN1_2") (pintype "input"))
    )
    (net (code "73") (name "Net-(S4-C)") (class "Default")
      (node (ref "R15") (pin "2") (pinfunction "2_2") (pintype "passive"))
      (node (ref "S4") (pin "2") (pinfunction "C_2") (pintype "bidirectional"))
    )
    (net (code "74") (name "Net-(S4-EM)") (class "Default")
      (node (ref "R14") (pin "1") (pinfunction "1_1") (pintype "passive"))
      (node (ref "S4") (pin "3") (pinfunction "EM_3") (pintype "bidirectional"))
      (node (ref "U1") (pin "6") (pinfunction "-IN2_6") (pintype "input"))
    )
    (net (code "75") (name "Net-(S5-C)") (class "Default")
      (node (ref "R18") (pin "2") (pinfunction "2_2") (pintype "passive"))
      (node (ref "S5") (pin "2") (pinfunction "C_2") (pintype "bidirectional"))
    )
    (net (code "76") (name "Net-(S5-EM)") (class "Default")
      (node (ref "R17") (pin "1") (pinfunction "1_1") (pintype "passive"))
      (node (ref "S5") (pin "3") (pinfunction "EM_3") (pintype "bidirectional"))
      (node (ref "U3") (pin "2") (pinfunction "-IN1_2") (pintype "input"))
    )
    (net (code "77") (name "Net-(U5-STAT)") (class "Default")
      (node (ref "D23") (pin "+") (pinfunction "+_+") (pintype "passive"))
      (node (ref "D24") (pin "-") (pinfunction "-_-") (pintype "passive"))
      (node (ref "R34") (pin "2") (pinfunction "2_2") (pintype "passive"))
      (node (ref "U5") (pin "5") (pinfunction "STAT_5") (pintype "output"))
    )
    (net (code "78") (name "Net-(U5-TS)") (class "Default")
      (node (ref "R36") (pin "2") (pinfunction "2_2") (pintype "passive"))
      (node (ref "R38") (pin "1") (pinfunction "1_1") (pintype "passive"))
      (node (ref "U5") (pin "4") (pinfunction "TS_4") (pintype "input"))
    )
    (net (code "79") (name "Net-(U6-IN)") (class "Default")
      (node (ref "C11") (pin "+") (pinfunction "+_+") (pintype "passive"))
      (node (ref "D14") (pin "-") (pinfunction "-_-") (pintype "passive"))
      (node (ref "U6") (pin "1") (pinfunction "IN_1") (pintype "bidirectional"))
    )
    (net (code "80") (name "Net-(U7-COMP)") (class "Default")
      (node (ref "R32") (pin "1") (pinfunction "1_1") (pintype "passive"))
      (node (ref "U7") (pin "1") (pinfunction "COMP_1") (pintype "bidirectional"))
    )
    (net (code "81") (name "Net-(U7-FB)") (class "Default")
      (node (ref "R40") (pin "2") (pinfunction "2_2") (pintype "passive"))
      (node (ref "R41") (pin "2") (pinfunction "2_2") (pintype "passive"))
      (node (ref "U7") (pin "2") (pinfunction "FB_2") (pintype "input"))
    )
    (net (code "82") (name "Net-(U7-LX)") (class "Default")
      (node (ref "D22") (pin "+") (pinfunction "+_+") (pintype "passive"))
      (node (ref "L1") (pin "1") (pinfunction "1_1") (pintype "passive"))
      (node (ref "U7") (pin "5") (pinfunction "LX_5") (pintype "output"))
    )
    (net (code "83") (name "Net-(U7-SS)") (class "Default")
      (node (ref "C18") (pin "1") (pinfunction "1_1") (pintype "passive"))
      (node (ref "U7") (pin "8") (pinfunction "SS_8") (pintype "bidirectional"))
    )
    (net (code "84") (name "unconnected-(J6-DM-Pad2)") (class "Default")
      (node (ref "J6") (pin "2") (pinfunction "DM_2") (pintype "bidirectional"))
    )
    (net (code "85") (name "unconnected-(J6-DP-Pad3)") (class "Default")
      (node (ref "J6") (pin "3") (pinfunction "DP_3") (pintype "bidirectional"))
    )
    (net (code "86") (name "unconnected-(J6-ID-Pad4)") (class "Default")
      (node (ref "J6") (pin "4") (pinfunction "ID_4") (pintype "bidirectional"))
    )
    (net (code "87") (name "unconnected-(SW1-PadCH1B)") (class "Default")
      (node (ref "SW1") (pin "CH1B") (pinfunction "CH1B_CH1B") (pintype "bidirectional"))
    )
    (net (code "88") (name "unconnected-(SW1-PadCH2B)") (class "Default")
      (node (ref "SW1") (pin "CH2B") (pinfunction "CH2B_CH2B") (pintype "bidirectional"))
    )
    (net (code "89") (name "unconnected-(U3B-OUT2-Pad7)") (class "Default")
      (node (ref "U3") (pin "7") (pinfunction "OUT2_7") (pintype "output"))
    )
    (net (code "90") (name "unconnected-(U4-NC-PadP$3)") (class "Default")
      (node (ref "U4") (pin "P$3") (pinfunction "NC_P$3") (pintype "bidirectional"))
    )
    (net (code "91") (name "unconnected-(U4-NC-PadP$18)") (class "Default")
      (node (ref "U4") (pin "P$18") (pinfunction "NC_P$18") (pintype "bidirectional"))
    )
    (net (code "92") (name "unconnected-(U13-GND-Pad33)") (class "Default")
      (node (ref "U13") (pin "33") (pinfunction "GND_33") (pintype "bidirectional"))
    )
    (net (code "93") (name "unconnected-(U13-MISO-Pad36)") (class "Default")
      (node (ref "U13") (pin "36") (pinfunction "MISO_36") (pintype "bidirectional"))
    )
    (net (code "94") (name "unconnected-(U13-MOSI-Pad32)") (class "Default")
      (node (ref "U13") (pin "32") (pinfunction "MOSI_32") (pintype "bidirectional"))
    )
    (net (code "95") (name "unconnected-(U13-RST-Pad34)") (class "Default")
      (node (ref "U13") (pin "34") (pinfunction "RST_34") (pintype "bidirectional"))
    )
    (net (code "96") (name "unconnected-(U13-SCK-Pad35)") (class "Default")
      (node (ref "U13") (pin "35") (pinfunction "SCK_35") (pintype "bidirectional"))
    )
    (net (code "97") (name "unconnected-(U13-VCC-Pad31)") (class "Default")
      (node (ref "U13") (pin "31") (pinfunction "VCC_31") (pintype "bidirectional"))
    )
  )
)
